# XStepper_Opto-Isolator_ADuM1301_v002.net
KiCad netlist of a schematic drawn in EAGLE
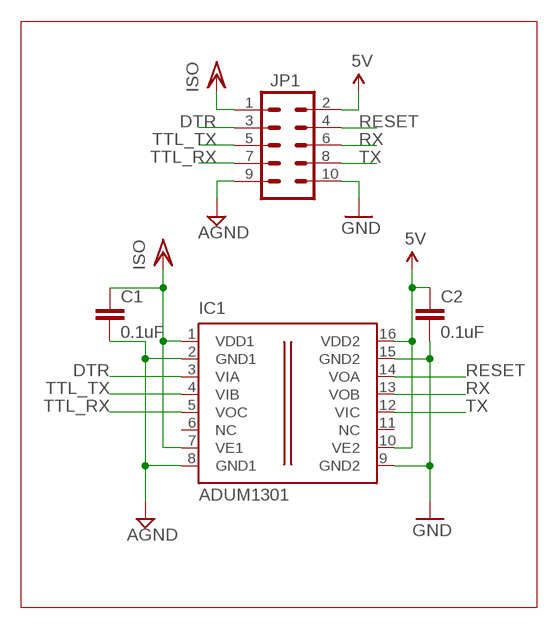
[diagram p0: schematic, sheet 1]

(export (version "E")
  (design (tool "Eeschema 10.0.6"))
  (components
    (comp (ref "C1")
      (value "0.1uF")
      (footprint "eagle-import:0805")
      (libsource (lib "eagle-import") (part "CAP0805"))
    )
    (comp (ref "C2")
      (value "0.1uF")
      (footprint "eagle-import:0805")
      (libsource (lib "eagle-import") (part "CAP0805"))
    )
    (comp (ref "IC1")
      (value "ADUM1301")
      (footprint "eagle-import:SO-16W")
      (fields (field (name "MPN") "ADUM1301BRWZ"))
      (libsource (lib "eagle-import") (part "ADUM1301"))
    )
    (comp (ref "JP1")
      (value "M05X2PTH")
      (footprint "eagle-import:AVR_ICSP")
      (libsource (lib "eagle-import") (part "M05X2PTH"))
    )
  )
  (nets
    (net (code "1") (name "/DTR") (class "Default")
      (node (ref "IC1") (pin "3") (pinfunction "VIA_3") (pintype "input"))
      (node (ref "JP1") (pin "3") (pinfunction "3_3") (pintype "passive"))
    )
    (net (code "2") (name "/RESET") (class "Default")
      (node (ref "IC1") (pin "14") (pinfunction "VOA_14") (pintype "tri_state"))
      (node (ref "JP1") (pin "4") (pinfunction "4_4") (pintype "passive"))
    )
    (net (code "3") (name "/RX") (class "Default")
      (node (ref "IC1") (pin "13") (pinfunction "VOB_13") (pintype "tri_state"))
      (node (ref "JP1") (pin "6") (pinfunction "6_6") (pintype "passive"))
    )
    (net (code "4") (name "/TTL_RX") (class "Default")
      (node (ref "IC1") (pin "5") (pinfunction "VOC_5") (pintype "tri_state"))
      (node (ref "JP1") (pin "7") (pinfunction "7_7") (pintype "passive"))
    )
    (net (code "5") (name "/TTL_TX") (class "Default")
      (node (ref "IC1") (pin "4") (pinfunction "VIB_4") (pintype "input"))
      (node (ref "JP1") (pin "5") (pinfunction "5_5") (pintype "passive"))
    )
    (net (code "6") (name "/TX") (class "Default")
      (node (ref "IC1") (pin "12") (pinfunction "VIC_12") (pintype "input"))
      (node (ref "JP1") (pin "8") (pinfunction "8_8") (pintype "passive"))
    )
    (net (code "7") (name "5V") (class "Default")
      (node (ref "C2") (pin "1") (pinfunction "1_1") (pintype "passive"))
      (node (ref "IC1") (pin "10") (pinfunction "VE2_10") (pintype "input"))
      (node (ref "IC1") (pin "16") (pinfunction "VDD2_16") (pintype "input"))
      (node (ref "JP1") (pin "2") (pinfunction "2_2") (pintype "passive"))
    )
    (net (code "8") (name "AGND") (class "Default")
      (node (ref "C1") (pin "2") (pinfunction "2_2") (pintype "passive"))
      (node (ref "IC1") (pin "2") (pinfunction "GND1_2") (pintype "input"))
      (node (ref "IC1") (pin "8") (pinfunction "GND1_8") (pintype "input"))
      (node (ref "JP1") (pin "9") (pinfunction "9_9") (pintype "passive"))
    )
    (net (code "9") (name "GND") (class "Default")
      (node (ref "C2") (pin "2") (pinfunction "2_2") (pintype "passive"))
      (node (ref "IC1") (pin "15") (pinfunction "GND2_15") (pintype "input"))
      (node (ref "IC1") (pin "9") (pinfunction "GND2_9") (pintype "input"))
      (node (ref "JP1") (pin "10") (pinfunction "10_10") (pintype "passive"))
    )
    (net (code "10") (name "ISO") (class "Default")
      (node (ref "C1") (pin "1") (pinfunction "1_1") (pintype "passive"))
      (node (ref "IC1") (pin "1") (pinfunction "VDD1_1") (pintype "input"))
      (node (ref "IC1") (pin "7") (pinfunction "VE1_7") (pintype "input"))
      (node (ref "JP1") (pin "1") (pinfunction "1_1") (pintype "passive"))
    )
    (net (code "11") (name "unconnected-(IC1-NC-Pad6)") (class "Default")
      (node (ref "IC1") (pin "6") (pinfunction "NC_6") (pintype "no_connect"))
    )
    (net (code "12") (name "unconnected-(IC1-NC-Pad11)") (class "Default")
      (node (ref "IC1") (pin "11") (pinfunction "NC_11") (pintype "no_connect"))
    )
  )
)
